# power.net
KiCad netlist of a schematic drawn in Altium Designer
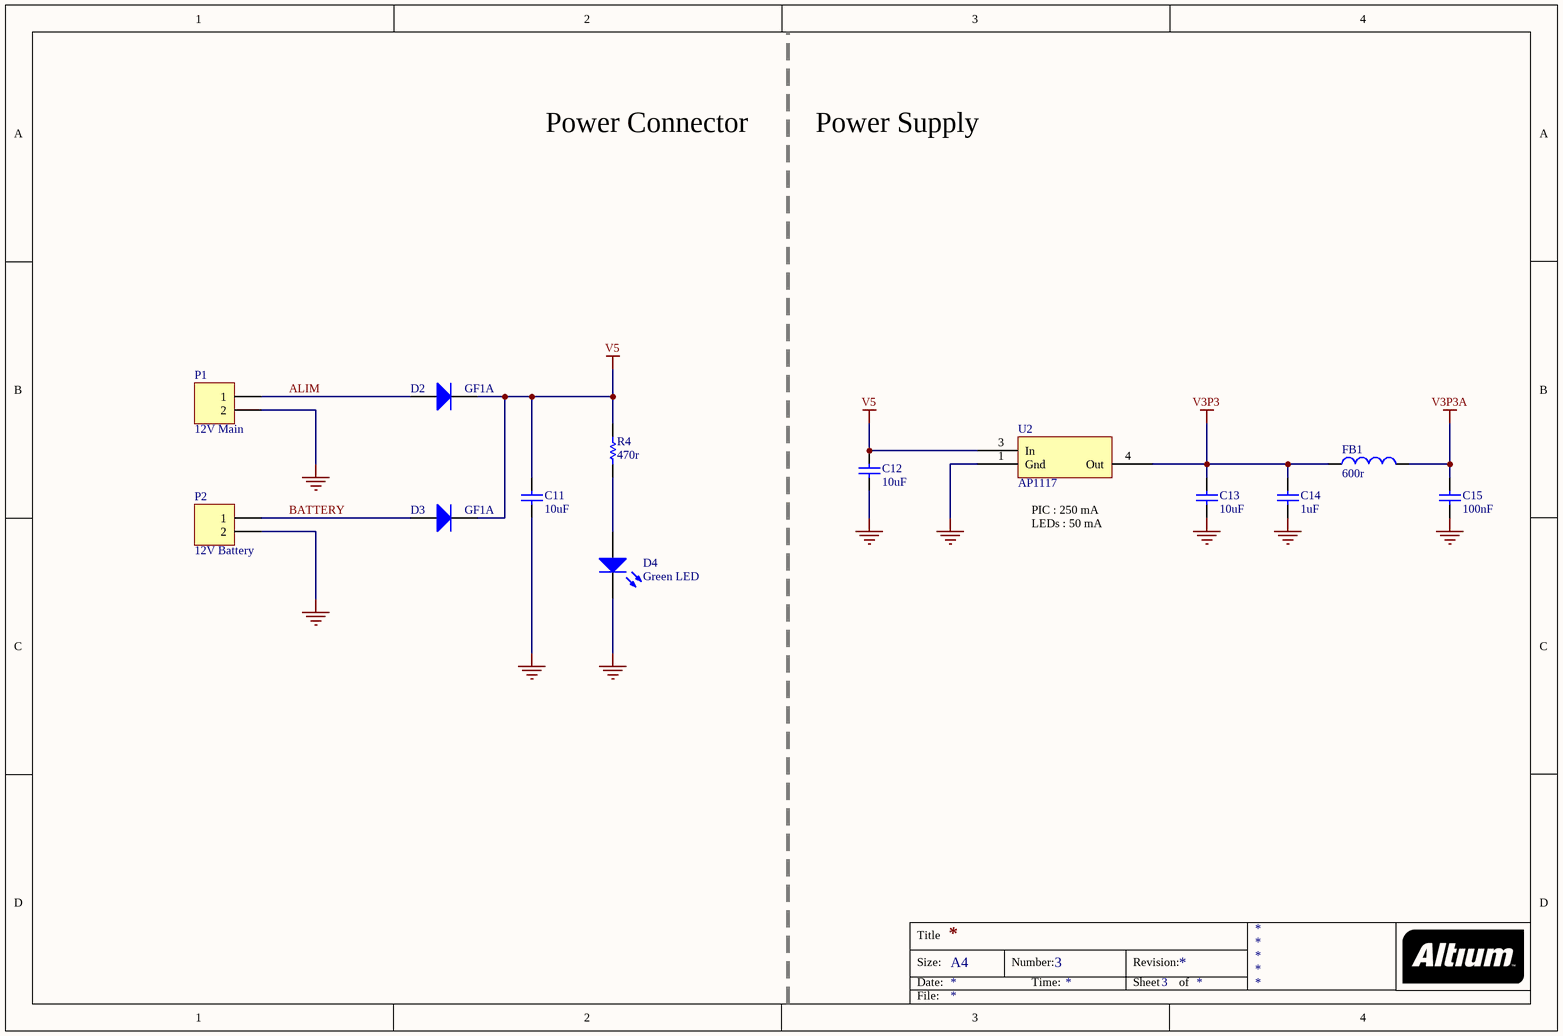
[diagram p0: power.SchDoc]

(export (version "E")
  (design (tool "Eeschema 10.0.6"))
  (components
    (comp (ref "C11")
      (value "10uF")
      (footprint "CAPC2012N")
      (description "Capacitor")
      (fields (field (name "PUBLISHER") "Altium Limited"))
      (libsource (lib "Miscellaneous Devices") (part "Cap"))
    )
    (comp (ref "C12")
      (value "10uF")
      (footprint "CAPC2012N")
      (description "Capacitor")
      (fields (field (name "PUBLISHER") "Altium Limited"))
      (libsource (lib "Miscellaneous Devices") (part "Cap"))
    )
    (comp (ref "C13")
      (value "10uF")
      (footprint "CAPC2012N")
      (description "Capacitor")
      (fields (field (name "PUBLISHER") "Altium Limited"))
      (libsource (lib "Miscellaneous Devices") (part "Cap"))
    )
    (comp (ref "C14")
      (value "1uF")
      (footprint "CAPC1608N")
      (description "Capacitor")
      (fields (field (name "PUBLISHER") "Altium Limited"))
      (libsource (lib "Miscellaneous Devices") (part "Cap"))
    )
    (comp (ref "C15")
      (value "100nF")
      (footprint "CAPC1608N")
      (description "Capacitor")
      (fields (field (name "PUBLISHER") "Altium Limited"))
      (libsource (lib "Miscellaneous Devices") (part "Cap"))
    )
    (comp (ref "D2")
      (value "GF1A")
      (footprint "SMA/DO-214AC_21")
      (description "Default Diode")
      (fields (field (name "PUBLISHER") "Altium Limited"))
      (libsource (lib "Miscellaneous Devices") (part "Diode"))
    )
    (comp (ref "D3")
      (value "GF1A")
      (footprint "SMA/DO-214AC_21")
      (description "Default Diode")
      (fields (field (name "PUBLISHER") "Altium Limited"))
      (libsource (lib "Miscellaneous Devices") (part "Diode"))
    )
    (comp (ref "D4")
      (value "Green LED")
      (footprint "LED 0805")
      (description "Typical INFRARED GaAs LED")
      (fields (field (name "PUBLISHER") "Altium Limited"))
      (libsource (lib "Miscellaneous Devices") (part "LED2"))
    )
    (comp (ref "FB1")
      (value "600r")
      (footprint "INDC1608AN")
      (description "Inductor")
      (fields (field (name "PUBLISHER") "Altium Limited"))
      (libsource (lib "Miscellaneous Devices") (part "Inductor"))
    )
    (comp (ref "P1")
      (value "12V Main")
      (footprint "PHOENIX_1985195")
      (description "Header, 2-Pin")
      (fields (field (name "PUBLISHER") "Altium Limited"))
      (libsource (lib "Miscellaneous Connectors") (part "Header 2"))
    )
    (comp (ref "P2")
      (value "12V Battery")
      (footprint "PHOENIX_1985195")
      (description "Header, 2-Pin")
      (fields (field (name "PUBLISHER") "Altium Limited"))
      (libsource (lib "Miscellaneous Connectors") (part "Header 2"))
    )
    (comp (ref "R4")
      (value "470r")
      (footprint "RESC1608N")
      (description "Resistor")
      (fields (field (name "PUBLISHER") "Altium Limited"))
      (libsource (lib "Miscellaneous Devices") (part "Res1"))
    )
    (comp (ref "U2")
      (value "AP1117")
      (footprint "TD03B_N")
      (description "1A LDO, 18V input, DPAK")
      (libsource (lib "Schlib1") (part "AP1117"))
    )
  )
  (nets
    (net (code "1") (name "/ALIM") (class "Default")
      (node (ref "D2") (pin "1") (pinfunction "A_1") (pintype "passive"))
      (node (ref "P1") (pin "1") (pinfunction "1_1") (pintype "passive"))
    )
    (net (code "2") (name "/BATTERY") (class "Default")
      (node (ref "D3") (pin "1") (pinfunction "A_1") (pintype "passive"))
      (node (ref "P2") (pin "1") (pinfunction "1_1") (pintype "passive"))
    )
    (net (code "3") (name "GND") (class "Default")
      (node (ref "C11") (pin "1") (pinfunction "1_1") (pintype "passive"))
      (node (ref "C12") (pin "1") (pinfunction "1_1") (pintype "passive"))
      (node (ref "C13") (pin "1") (pinfunction "1_1") (pintype "passive"))
      (node (ref "C14") (pin "1") (pinfunction "1_1") (pintype "passive"))
      (node (ref "C15") (pin "1") (pinfunction "1_1") (pintype "passive"))
      (node (ref "D4") (pin "2") (pinfunction "K_2") (pintype "passive"))
      (node (ref "P1") (pin "2") (pinfunction "2_2") (pintype "passive"))
      (node (ref "P2") (pin "2") (pinfunction "2_2") (pintype "passive"))
      (node (ref "U2") (pin "1") (pinfunction "Gnd_1") (pintype "power_in"))
    )
    (net (code "4") (name "Net-(D4-A)") (class "Default")
      (node (ref "D4") (pin "1") (pinfunction "A_1") (pintype "passive"))
      (node (ref "R4") (pin "1") (pinfunction "1_1") (pintype "passive"))
    )
    (net (code "5") (name "V3P3") (class "Default")
      (node (ref "C13") (pin "2") (pinfunction "2_2") (pintype "passive"))
      (node (ref "C14") (pin "2") (pinfunction "2_2") (pintype "passive"))
      (node (ref "FB1") (pin "1") (pinfunction "1_1") (pintype "passive"))
      (node (ref "U2") (pin "4") (pinfunction "Out_4") (pintype "power_in"))
    )
    (net (code "6") (name "V3P3A") (class "Default")
      (node (ref "C15") (pin "2") (pinfunction "2_2") (pintype "passive"))
      (node (ref "FB1") (pin "2") (pinfunction "2_2") (pintype "passive"))
    )
    (net (code "7") (name "V5") (class "Default")
      (node (ref "C11") (pin "2") (pinfunction "2_2") (pintype "passive"))
      (node (ref "C12") (pin "2") (pinfunction "2_2") (pintype "passive"))
      (node (ref "D2") (pin "2") (pinfunction "K_2") (pintype "passive"))
      (node (ref "D3") (pin "2") (pinfunction "K_2") (pintype "passive"))
      (node (ref "R4") (pin "2") (pinfunction "2_2") (pintype "passive"))
      (node (ref "U2") (pin "3") (pinfunction "In_3") (pintype "power_in"))
    )
  )
)
